# Sheet1.net
KiCad netlist of a schematic drawn in Altium Designer
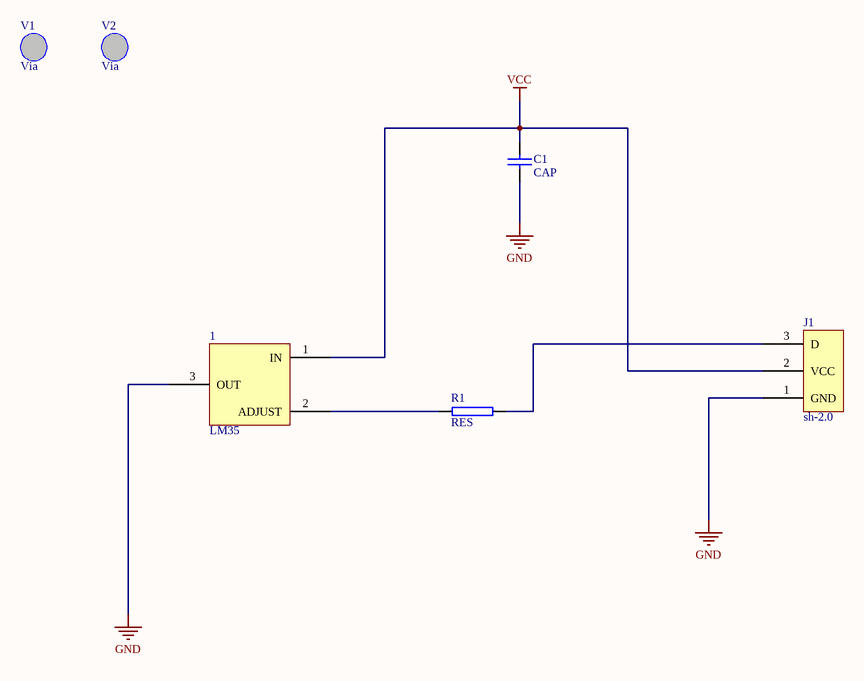
[diagram p0: Sheet1.SchDoc]

(export (version "E")
  (design (tool "Eeschema 10.0.6"))
  (components
    (comp (ref "1") (value "LM35") (footprint "TO-92") (libsource (lib "gupeng_sch") (part "LM317")))
    (comp (ref "C1")
      (value "CAP")
      (footprint "Miscellaneous Devices:1608[0603]")
      (libsource (lib "PEI_SCH") (part "CAP"))
    )
    (comp (ref "J1") (value "sh-2.0") (footprint "sh-2.0") (libsource (lib "zhangchong") (part "sh-2.0")))
    (comp (ref "R1")
      (value "RES")
      (footprint "Miscellaneous Devices:1608[0603]")
      (libsource (lib "gupeng_sch") (part "RES"))
    )
    (comp (ref "V1") (value "Via") (footprint "zhangchong:Via") (libsource (lib "zhangchong") (part "Via")))
    (comp (ref "V2") (value "Via") (footprint "zhangchong:Via") (libsource (lib "zhangchong") (part "Via")))
  )
  (nets
    (net (code "1") (name "GND") (class "Default")
      (node (ref "1") (pin "3") (pinfunction "OUT_3") (pintype "passive"))
      (node (ref "C1") (pin "2") (pinfunction "2_2") (pintype "passive"))
      (node (ref "J1") (pin "1") (pinfunction "GND_1") (pintype "passive"))
    )
    (net (code "2") (name "Net-(1-ADJUST)") (class "Default")
      (node (ref "1") (pin "2") (pinfunction "ADJUST_2") (pintype "passive"))
      (node (ref "R1") (pin "2") (pinfunction "2_2") (pintype "passive"))
    )
    (net (code "3") (name "Net-(J1-D)") (class "Default")
      (node (ref "J1") (pin "3") (pinfunction "D_3") (pintype "passive"))
      (node (ref "R1") (pin "1") (pinfunction "1_1") (pintype "passive"))
    )
    (net (code "4") (name "VCC") (class "Default")
      (node (ref "1") (pin "1") (pinfunction "IN_1") (pintype "passive"))
      (node (ref "C1") (pin "1") (pinfunction "1_1") (pintype "passive"))
      (node (ref "J1") (pin "2") (pinfunction "VCC_2") (pintype "passive"))
    )
  )
)
